# femtoUSB_r1_0_0.net
KiCad netlist of a schematic drawn in EAGLE
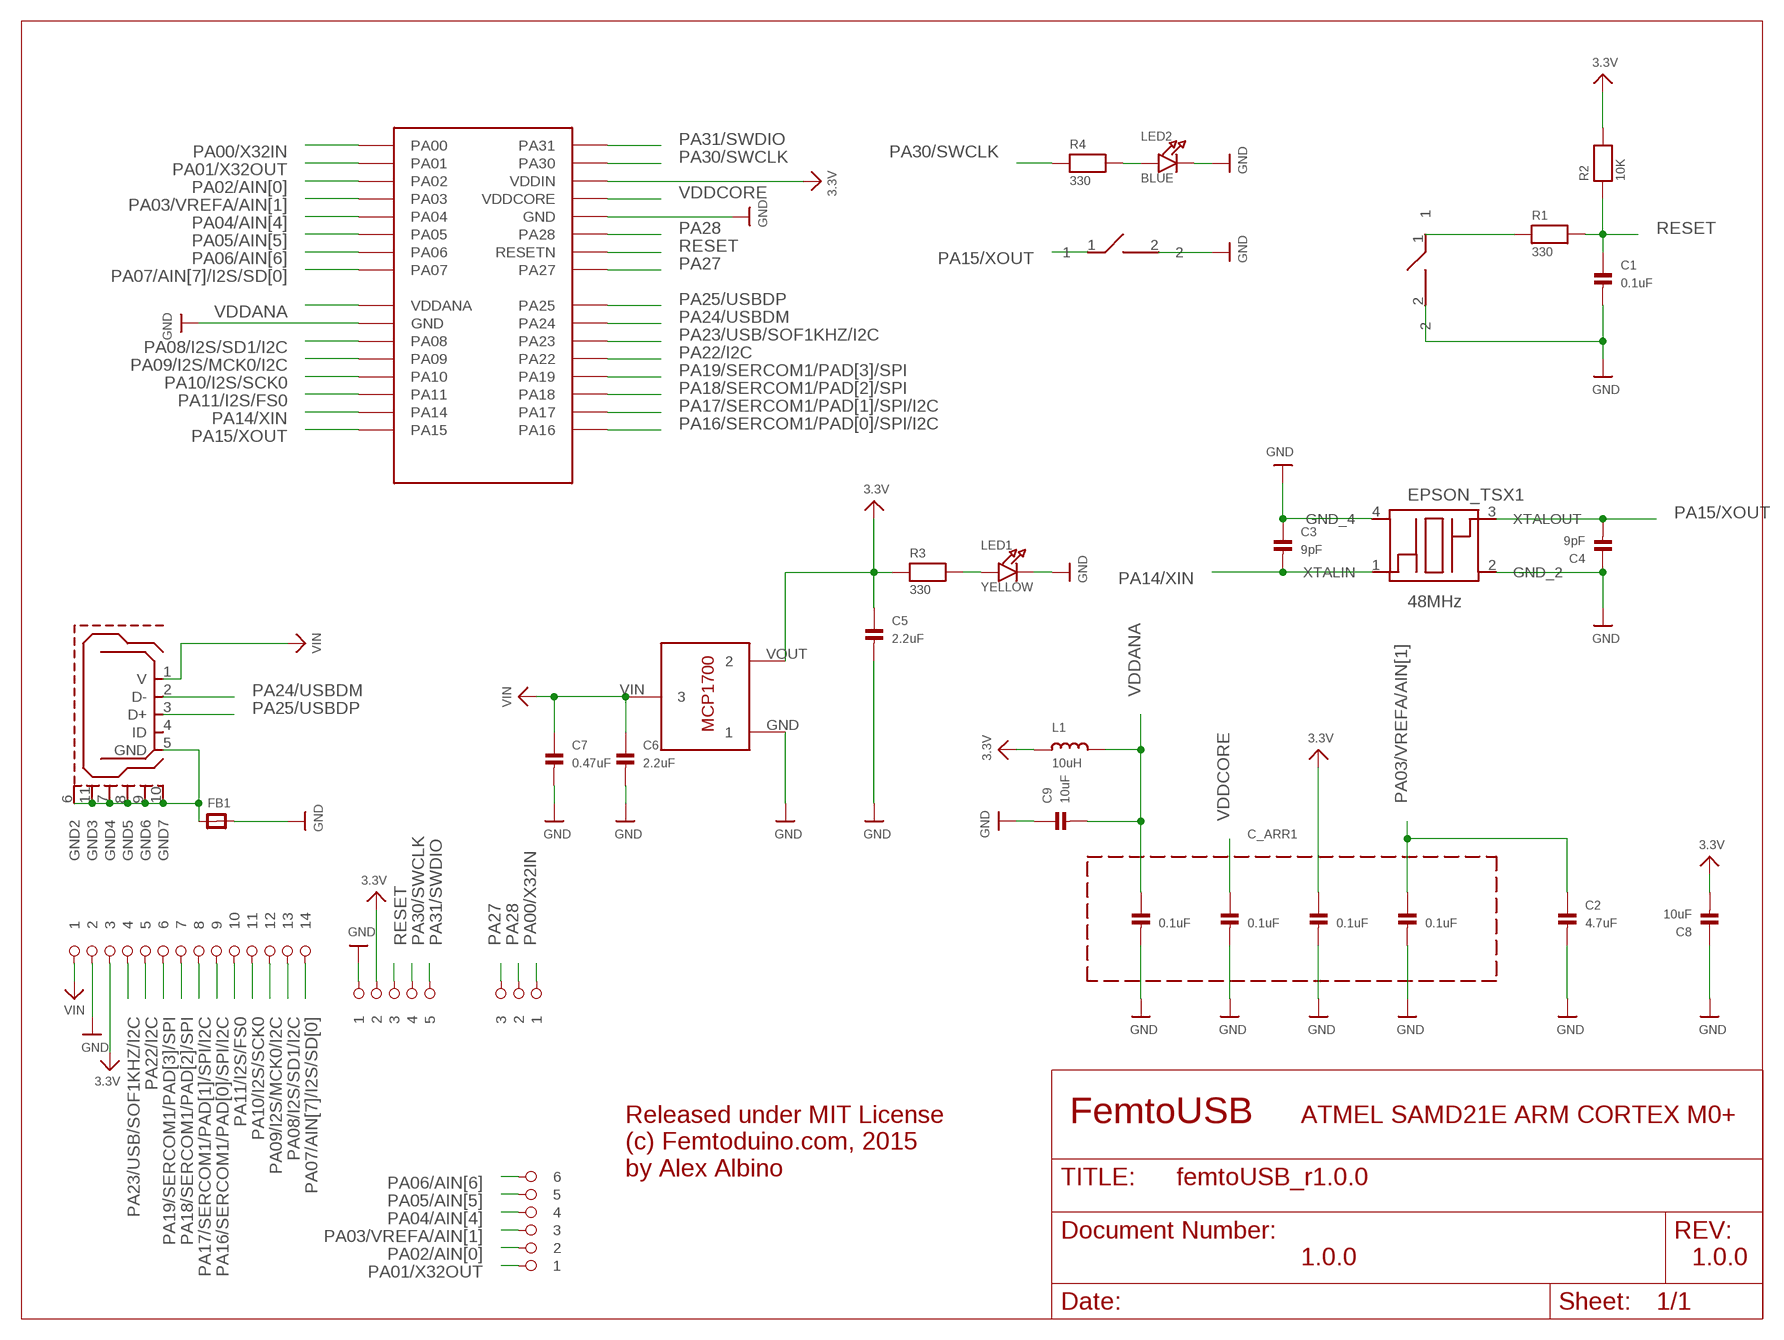
[diagram p0: schematic, sheet 1]

(export (version "E")
  (design (tool "Eeschema 10.0.6"))
  (components
    (comp (ref "BTN")
      (value "OMRON B3U-300P(M)")
      (footprint "eagle-import:SPST_SMD")
      (libsource (lib "eagle-import") (part "SPST_SMD"))
    )
    (comp (ref "C1")
      (value "0.1uF")
      (footprint "eagle-import:_0402MP")
      (libsource (lib "eagle-import") (part "CAP_CERAMIC_0402MP"))
    )
    (comp (ref "C2")
      (value "4.7uF")
      (footprint "eagle-import:_0402MP")
      (libsource (lib "eagle-import") (part "CAP_CERAMIC_0402MP"))
    )
    (comp (ref "C3")
      (value "9pF")
      (footprint "eagle-import:_0402MP")
      (libsource (lib "eagle-import") (part "CAP_CERAMIC_0402MP"))
    )
    (comp (ref "C4")
      (value "9pF")
      (footprint "eagle-import:_0402MP")
      (libsource (lib "eagle-import") (part "CAP_CERAMIC_0402MP"))
    )
    (comp (ref "C5")
      (value "2.2uF")
      (footprint "eagle-import:_0402MP")
      (libsource (lib "eagle-import") (part "CAP_CERAMIC_0402MP"))
    )
    (comp (ref "C6")
      (value "2.2uF")
      (footprint "eagle-import:_0402MP")
      (libsource (lib "eagle-import") (part "CAP_CERAMIC_0402MP"))
    )
    (comp (ref "C7")
      (value "0.47uF")
      (footprint "eagle-import:_0402MP")
      (libsource (lib "eagle-import") (part "CAP_CERAMIC_0402MP"))
    )
    (comp (ref "C8")
      (value "10uF")
      (footprint "eagle-import:_0402MP")
      (libsource (lib "eagle-import") (part "CAP_CERAMIC_0402MP"))
    )
    (comp (ref "C9")
      (value "10uF")
      (footprint "eagle-import:_0402MP")
      (libsource (lib "eagle-import") (part "CAP_CERAMIC_0402MP"))
    )
    (comp (ref "C_ARR1")
      (value "0.1uF")
      (footprint "eagle-import:CAPACITOR_ARRAY_1206_MONO_1X4")
      (libsource (lib "eagle-import") (part "KEMET_CERAMIC_CAPACITOR_ARRAY_1X4"))
    )
    (comp (ref "EPSON_TSX1")
      (value "48MHz")
      (footprint "eagle-import:TSX-3225")
      (fields (field (name "DIGIKEY_PART") "TSX-3225 32.0000MF15X-B-ND"))
      (libsource (lib "eagle-import") (part "TSX-3225"))
    )
    (comp (ref "FB1")
      (value "FERRITE_0603MP")
      (footprint "eagle-import:_0603MP")
      (libsource (lib "eagle-import") (part "FERRITE_0603MP"))
    )
    (comp (ref "IC1")
      (value "ATSAMD21E18A-MUT")
      (footprint "eagle-import:QFN32")
      (libsource (lib "eagle-import") (part "ATSAMD21E18A-MUT"))
    )
    (comp (ref "L1")
      (value "10uH")
      (footprint "eagle-import:_0603MP")
      (libsource (lib "eagle-import") (part "INDUCTOR_0603MP"))
    )
    (comp (ref "LDO_VREG")
      (value "MCP1700T-3302E/TT")
      (footprint "eagle-import:MCP1700T-3302E_TT")
      (libsource (lib "eagle-import") (part "MCP1700T-3302E/TT"))
    )
    (comp (ref "LED1")
      (value "YELLOW")
      (footprint "eagle-import:CHIPLED_0603_NOOUTLINE")
      (libsource (lib "eagle-import") (part "LED0603_NOOUTLINE"))
    )
    (comp (ref "LED2")
      (value "BLUE")
      (footprint "eagle-import:CHIPLED_0603_NOOUTLINE")
      (libsource (lib "eagle-import") (part "LED0603_NOOUTLINE"))
    )
    (comp (ref "MICRO_B_USB")
      (value "USB_MICROB")
      (footprint "eagle-import:USB_MICROB_PACKAGE")
      (libsource (lib "eagle-import") (part "USB_MICROB"))
    )
    (comp (ref "R1")
      (value "330")
      (footprint "eagle-import:_0402MP")
      (libsource (lib "eagle-import") (part "RESISTOR_0402MP"))
    )
    (comp (ref "R2")
      (value "10K")
      (footprint "eagle-import:_0402MP")
      (libsource (lib "eagle-import") (part "RESISTOR_0402MP"))
    )
    (comp (ref "R3")
      (value "330")
      (footprint "eagle-import:_0402MP")
      (libsource (lib "eagle-import") (part "RESISTOR_0402MP"))
    )
    (comp (ref "R4")
      (value "330")
      (footprint "eagle-import:_0402MP")
      (libsource (lib "eagle-import") (part "RESISTOR_0402MP"))
    )
    (comp (ref "U$6")
      (value "1X14_ROUND")
      (footprint "eagle-import:1X14_ROUND")
      (libsource (lib "eagle-import") (part "1X14_ROUND"))
    )
    (comp (ref "U$7")
      (value "1X3_ROUND")
      (footprint "eagle-import:1X3_ROUND")
      (libsource (lib "eagle-import") (part "1X3_ROUND"))
    )
    (comp (ref "U$9")
      (value "1X5_ROUND")
      (footprint "eagle-import:1X5_ROUND")
      (libsource (lib "eagle-import") (part "1X5_ROUND"))
    )
    (comp (ref "U$12")
      (value "1X6_ROUND")
      (footprint "eagle-import:1X6_ROUND")
      (libsource (lib "eagle-import") (part "1X6_ROUND"))
    )
    (comp (ref "U$38")
      (value "SPST_SMD")
      (footprint "eagle-import:SPST_SMD")
      (libsource (lib "eagle-import") (part "SPST_SMD"))
    )
  )
  (nets
    (net (code "1") (name "/PA00{slash}X32IN") (class "Default")
      (node (ref "IC1") (pin "1") (pinfunction "PA00_1") (pintype "bidirectional"))
      (node (ref "U$7") (pin "P$1") (pinfunction "1_P$1") (pintype "bidirectional"))
    )
    (net (code "2") (name "/PA01{slash}X32OUT") (class "Default")
      (node (ref "IC1") (pin "2") (pinfunction "PA01_2") (pintype "bidirectional"))
      (node (ref "U$12") (pin "P$1") (pinfunction "1_P$1") (pintype "bidirectional"))
    )
    (net (code "3") (name "/PA02{slash}AIN[0]") (class "Default")
      (node (ref "IC1") (pin "3") (pinfunction "PA02_3") (pintype "bidirectional"))
      (node (ref "U$12") (pin "P$2") (pinfunction "2_P$2") (pintype "bidirectional"))
    )
    (net (code "4") (name "/PA03{slash}VREFA{slash}AIN[1]") (class "Default")
      (node (ref "C2") (pin "1") (pinfunction "P$1_1") (pintype "passive"))
      (node (ref "C_ARR1") (pin "7") (pinfunction "P$7_7") (pintype "passive"))
      (node (ref "IC1") (pin "4") (pinfunction "PA03_4") (pintype "bidirectional"))
      (node (ref "U$12") (pin "P$3") (pinfunction "3_P$3") (pintype "bidirectional"))
    )
    (net (code "5") (name "/PA04{slash}AIN[4]") (class "Default")
      (node (ref "IC1") (pin "5") (pinfunction "PA04_5") (pintype "bidirectional"))
      (node (ref "U$12") (pin "P$4") (pinfunction "4_P$4") (pintype "bidirectional"))
    )
    (net (code "6") (name "/PA05{slash}AIN[5]") (class "Default")
      (node (ref "IC1") (pin "6") (pinfunction "PA05_6") (pintype "bidirectional"))
      (node (ref "U$12") (pin "P$5") (pinfunction "5_P$5") (pintype "bidirectional"))
    )
    (net (code "7") (name "/PA06{slash}AIN[6]") (class "Default")
      (node (ref "IC1") (pin "7") (pinfunction "PA06_7") (pintype "bidirectional"))
      (node (ref "U$12") (pin "P$6") (pinfunction "6_P$6") (pintype "bidirectional"))
    )
    (net (code "8") (name "/PA07{slash}AIN[7]{slash}I2S{slash}SD[0]") (class "Default")
      (node (ref "IC1") (pin "8") (pinfunction "PA07_8") (pintype "bidirectional"))
      (node (ref "U$6") (pin "P$14") (pinfunction "14_P$14") (pintype "bidirectional"))
    )
    (net (code "9") (name "/PA08{slash}I2S{slash}SD1{slash}I2C") (class "Default")
      (node (ref "IC1") (pin "11") (pinfunction "PA08_11") (pintype "bidirectional"))
      (node (ref "U$6") (pin "P$13") (pinfunction "13_P$13") (pintype "bidirectional"))
    )
    (net (code "10") (name "/PA09{slash}I2S{slash}MCK0{slash}I2C") (class "Default")
      (node (ref "IC1") (pin "12") (pinfunction "PA09_12") (pintype "bidirectional"))
      (node (ref "U$6") (pin "P$12") (pinfunction "12_P$12") (pintype "bidirectional"))
    )
    (net (code "11") (name "/PA10{slash}I2S{slash}SCK0") (class "Default")
      (node (ref "IC1") (pin "13") (pinfunction "PA10_13") (pintype "bidirectional"))
      (node (ref "U$6") (pin "P$11") (pinfunction "11_P$11") (pintype "bidirectional"))
    )
    (net (code "12") (name "/PA11{slash}I2S{slash}FS0") (class "Default")
      (node (ref "IC1") (pin "14") (pinfunction "PA11_14") (pintype "bidirectional"))
      (node (ref "U$6") (pin "P$10") (pinfunction "10_P$10") (pintype "bidirectional"))
    )
    (net (code "13") (name "/PA14{slash}XIN") (class "Default")
      (node (ref "C3") (pin "2") (pinfunction "P$2_2") (pintype "passive"))
      (node (ref "EPSON_TSX1") (pin "1") (pinfunction "XTALIN_1") (pintype "bidirectional"))
      (node (ref "IC1") (pin "15") (pinfunction "PA14_15") (pintype "bidirectional"))
    )
    (net (code "14") (name "/PA15{slash}XOUT") (class "Default")
      (node (ref "C4") (pin "2") (pinfunction "P$2_2") (pintype "passive"))
      (node (ref "EPSON_TSX1") (pin "3") (pinfunction "XTALOUT_3") (pintype "bidirectional"))
      (node (ref "IC1") (pin "16") (pinfunction "PA15_16") (pintype "bidirectional"))
      (node (ref "U$38") (pin "1") (pinfunction "1_1") (pintype "bidirectional"))
    )
    (net (code "15") (name "/PA16{slash}SERCOM1{slash}PAD[0]{slash}SPI{slash}I2C") (class "Default")
      (node (ref "IC1") (pin "17") (pinfunction "PA16_17") (pintype "bidirectional"))
      (node (ref "U$6") (pin "P$9") (pinfunction "9_P$9") (pintype "bidirectional"))
    )
    (net (code "16") (name "/PA17{slash}SERCOM1{slash}PAD[1]{slash}SPI{slash}I2C") (class "Default")
      (node (ref "IC1") (pin "18") (pinfunction "PA17_18") (pintype "bidirectional"))
      (node (ref "U$6") (pin "P$8") (pinfunction "8_P$8") (pintype "bidirectional"))
    )
    (net (code "17") (name "/PA18{slash}SERCOM1{slash}PAD[2]{slash}SPI") (class "Default")
      (node (ref "IC1") (pin "19") (pinfunction "PA18_19") (pintype "bidirectional"))
      (node (ref "U$6") (pin "P$7") (pinfunction "7_P$7") (pintype "bidirectional"))
    )
    (net (code "18") (name "/PA19{slash}SERCOM1{slash}PAD[3]{slash}SPI") (class "Default")
      (node (ref "IC1") (pin "20") (pinfunction "PA19_20") (pintype "bidirectional"))
      (node (ref "U$6") (pin "P$6") (pinfunction "6_P$6") (pintype "bidirectional"))
    )
    (net (code "19") (name "/PA22{slash}I2C") (class "Default")
      (node (ref "IC1") (pin "21") (pinfunction "PA22_21") (pintype "bidirectional"))
      (node (ref "U$6") (pin "P$5") (pinfunction "5_P$5") (pintype "bidirectional"))
    )
    (net (code "20") (name "/PA23{slash}USB{slash}SOF1KHZ{slash}I2C") (class "Default")
      (node (ref "IC1") (pin "22") (pinfunction "PA23_22") (pintype "bidirectional"))
      (node (ref "U$6") (pin "P$4") (pinfunction "4_P$4") (pintype "bidirectional"))
    )
    (net (code "21") (name "/PA24{slash}USBDM") (class "Default")
      (node (ref "IC1") (pin "23") (pinfunction "PA24_23") (pintype "bidirectional"))
      (node (ref "MICRO_B_USB") (pin "2") (pinfunction "D-_2") (pintype "bidirectional"))
    )
    (net (code "22") (name "/PA25{slash}USBDP") (class "Default")
      (node (ref "IC1") (pin "24") (pinfunction "PA25_24") (pintype "bidirectional"))
      (node (ref "MICRO_B_USB") (pin "3") (pinfunction "D+_3") (pintype "bidirectional"))
    )
    (net (code "23") (name "/PA27") (class "Default")
      (node (ref "IC1") (pin "25") (pinfunction "PA27_25") (pintype "bidirectional"))
      (node (ref "U$7") (pin "P$3") (pinfunction "3_P$3") (pintype "bidirectional"))
    )
    (net (code "24") (name "/PA28") (class "Default")
      (node (ref "IC1") (pin "27") (pinfunction "PA28_27") (pintype "bidirectional"))
      (node (ref "U$7") (pin "P$2") (pinfunction "2_P$2") (pintype "bidirectional"))
    )
    (net (code "25") (name "/PA30{slash}SWCLK") (class "Default")
      (node (ref "IC1") (pin "31") (pinfunction "PA30_31") (pintype "bidirectional"))
      (node (ref "R4") (pin "1") (pinfunction "1_1") (pintype "passive"))
      (node (ref "U$9") (pin "P$4") (pinfunction "4_P$4") (pintype "bidirectional"))
    )
    (net (code "26") (name "/PA31{slash}SWDIO") (class "Default")
      (node (ref "IC1") (pin "32") (pinfunction "PA31_32") (pintype "bidirectional"))
      (node (ref "U$9") (pin "P$5") (pinfunction "5_P$5") (pintype "bidirectional"))
    )
    (net (code "27") (name "/RESET") (class "Default")
      (node (ref "C1") (pin "1") (pinfunction "P$1_1") (pintype "passive"))
      (node (ref "IC1") (pin "26") (pinfunction "RESETN_26") (pintype "bidirectional"))
      (node (ref "R1") (pin "2") (pinfunction "2_2") (pintype "passive"))
      (node (ref "R2") (pin "1") (pinfunction "1_1") (pintype "passive"))
      (node (ref "U$9") (pin "P$3") (pinfunction "3_P$3") (pintype "bidirectional"))
    )
    (net (code "28") (name "/VDDANA") (class "Default")
      (node (ref "C9") (pin "2") (pinfunction "P$2_2") (pintype "passive"))
      (node (ref "C_ARR1") (pin "1") (pinfunction "P$1_1") (pintype "passive"))
      (node (ref "IC1") (pin "9") (pinfunction "VDDANA_9") (pintype "bidirectional"))
      (node (ref "L1") (pin "2") (pinfunction "2_2") (pintype "passive"))
    )
    (net (code "29") (name "/VDDCORE") (class "Default")
      (node (ref "C_ARR1") (pin "3") (pinfunction "P$3_3") (pintype "passive"))
      (node (ref "IC1") (pin "29") (pinfunction "VDDCORE_29") (pintype "bidirectional"))
    )
    (net (code "30") (name "3.3V") (class "Default")
      (node (ref "C5") (pin "1") (pinfunction "P$1_1") (pintype "passive"))
      (node (ref "C8") (pin "2") (pinfunction "P$2_2") (pintype "passive"))
      (node (ref "C_ARR1") (pin "5") (pinfunction "P$5_5") (pintype "passive"))
      (node (ref "IC1") (pin "30") (pinfunction "VDDIN_30") (pintype "bidirectional"))
      (node (ref "L1") (pin "1") (pinfunction "1_1") (pintype "passive"))
      (node (ref "LDO_VREG") (pin "VOUT") (pinfunction "2_VOUT") (pintype "bidirectional"))
      (node (ref "R2") (pin "2") (pinfunction "2_2") (pintype "passive"))
      (node (ref "R3") (pin "1") (pinfunction "1_1") (pintype "passive"))
      (node (ref "U$6") (pin "P$3") (pinfunction "3_P$3") (pintype "bidirectional"))
      (node (ref "U$9") (pin "P$2") (pinfunction "2_P$2") (pintype "bidirectional"))
    )
    (net (code "31") (name "GND") (class "Default")
      (node (ref "BTN") (pin "2") (pinfunction "2_2") (pintype "bidirectional"))
      (node (ref "C1") (pin "2") (pinfunction "P$2_2") (pintype "passive"))
      (node (ref "C2") (pin "2") (pinfunction "P$2_2") (pintype "passive"))
      (node (ref "C3") (pin "1") (pinfunction "P$1_1") (pintype "passive"))
      (node (ref "C4") (pin "1") (pinfunction "P$1_1") (pintype "passive"))
      (node (ref "C5") (pin "2") (pinfunction "P$2_2") (pintype "passive"))
      (node (ref "C6") (pin "2") (pinfunction "P$2_2") (pintype "passive"))
      (node (ref "C7") (pin "2") (pinfunction "P$2_2") (pintype "passive"))
      (node (ref "C8") (pin "1") (pinfunction "P$1_1") (pintype "passive"))
      (node (ref "C9") (pin "1") (pinfunction "P$1_1") (pintype "passive"))
      (node (ref "C_ARR1") (pin "2") (pinfunction "P$2_2") (pintype "passive"))
      (node (ref "C_ARR1") (pin "4") (pinfunction "P$4_4") (pintype "passive"))
      (node (ref "C_ARR1") (pin "6") (pinfunction "P$6_6") (pintype "passive"))
      (node (ref "C_ARR1") (pin "8") (pinfunction "P$8_8") (pintype "passive"))
      (node (ref "EPSON_TSX1") (pin "2") (pinfunction "GND_2_2") (pintype "bidirectional"))
      (node (ref "EPSON_TSX1") (pin "4") (pinfunction "GND_4_4") (pintype "bidirectional"))
      (node (ref "FB1") (pin "2") (pinfunction "P$2_2") (pintype "passive"))
      (node (ref "IC1") (pin "10") (pinfunction "GND_10") (pintype "bidirectional"))
      (node (ref "IC1") (pin "28") (pinfunction "GND_28") (pintype "bidirectional"))
      (node (ref "LDO_VREG") (pin "GND") (pinfunction "1_GND") (pintype "bidirectional"))
      (node (ref "LED1") (pin "C") (pinfunction "C_C") (pintype "passive"))
      (node (ref "LED2") (pin "C") (pinfunction "C_C") (pintype "passive"))
      (node (ref "U$38") (pin "2") (pinfunction "2_2") (pintype "bidirectional"))
      (node (ref "U$6") (pin "P$2") (pinfunction "2_P$2") (pintype "bidirectional"))
      (node (ref "U$9") (pin "P$1") (pinfunction "1_P$1") (pintype "bidirectional"))
    )
    (net (code "32") (name "Net-(BTN-Pad1)") (class "Default")
      (node (ref "BTN") (pin "1") (pinfunction "1_1") (pintype "bidirectional"))
      (node (ref "R1") (pin "1") (pinfunction "1_1") (pintype "passive"))
    )
    (net (code "33") (name "Net-(FB1-P$1)") (class "Default")
      (node (ref "FB1") (pin "1") (pinfunction "P$1_1") (pintype "passive"))
      (node (ref "MICRO_B_USB") (pin "10") (pinfunction "GND7_10") (pintype "bidirectional"))
      (node (ref "MICRO_B_USB") (pin "11") (pinfunction "GND3_11") (pintype "bidirectional"))
      (node (ref "MICRO_B_USB") (pin "5") (pinfunction "GND_5") (pintype "bidirectional"))
      (node (ref "MICRO_B_USB") (pin "6") (pinfunction "GND2_6") (pintype "bidirectional"))
      (node (ref "MICRO_B_USB") (pin "7") (pinfunction "GND4_7") (pintype "bidirectional"))
      (node (ref "MICRO_B_USB") (pin "8") (pinfunction "GND5_8") (pintype "bidirectional"))
      (node (ref "MICRO_B_USB") (pin "9") (pinfunction "GND6_9") (pintype "bidirectional"))
    )
    (net (code "34") (name "Net-(LED1-PadA)") (class "Default")
      (node (ref "LED1") (pin "A") (pinfunction "A_A") (pintype "passive"))
      (node (ref "R3") (pin "2") (pinfunction "2_2") (pintype "passive"))
    )
    (net (code "35") (name "Net-(LED2-PadA)") (class "Default")
      (node (ref "LED2") (pin "A") (pinfunction "A_A") (pintype "passive"))
      (node (ref "R4") (pin "2") (pinfunction "2_2") (pintype "passive"))
    )
    (net (code "36") (name "VIN") (class "Default")
      (node (ref "C6") (pin "1") (pinfunction "P$1_1") (pintype "passive"))
      (node (ref "C7") (pin "1") (pinfunction "P$1_1") (pintype "passive"))
      (node (ref "LDO_VREG") (pin "VIN") (pinfunction "3_VIN") (pintype "bidirectional"))
      (node (ref "MICRO_B_USB") (pin "1") (pinfunction "V_1") (pintype "bidirectional"))
      (node (ref "U$6") (pin "P$1") (pinfunction "1_P$1") (pintype "bidirectional"))
    )
    (net (code "37") (name "unconnected-(MICRO_B_USB-ID-Pad4)") (class "Default")
      (node (ref "MICRO_B_USB") (pin "4") (pinfunction "ID_4") (pintype "bidirectional"))
    )
  )
)
